# solenoid_valve_slave_circuit.net
KiCad netlist of a schematic drawn in EAGLE
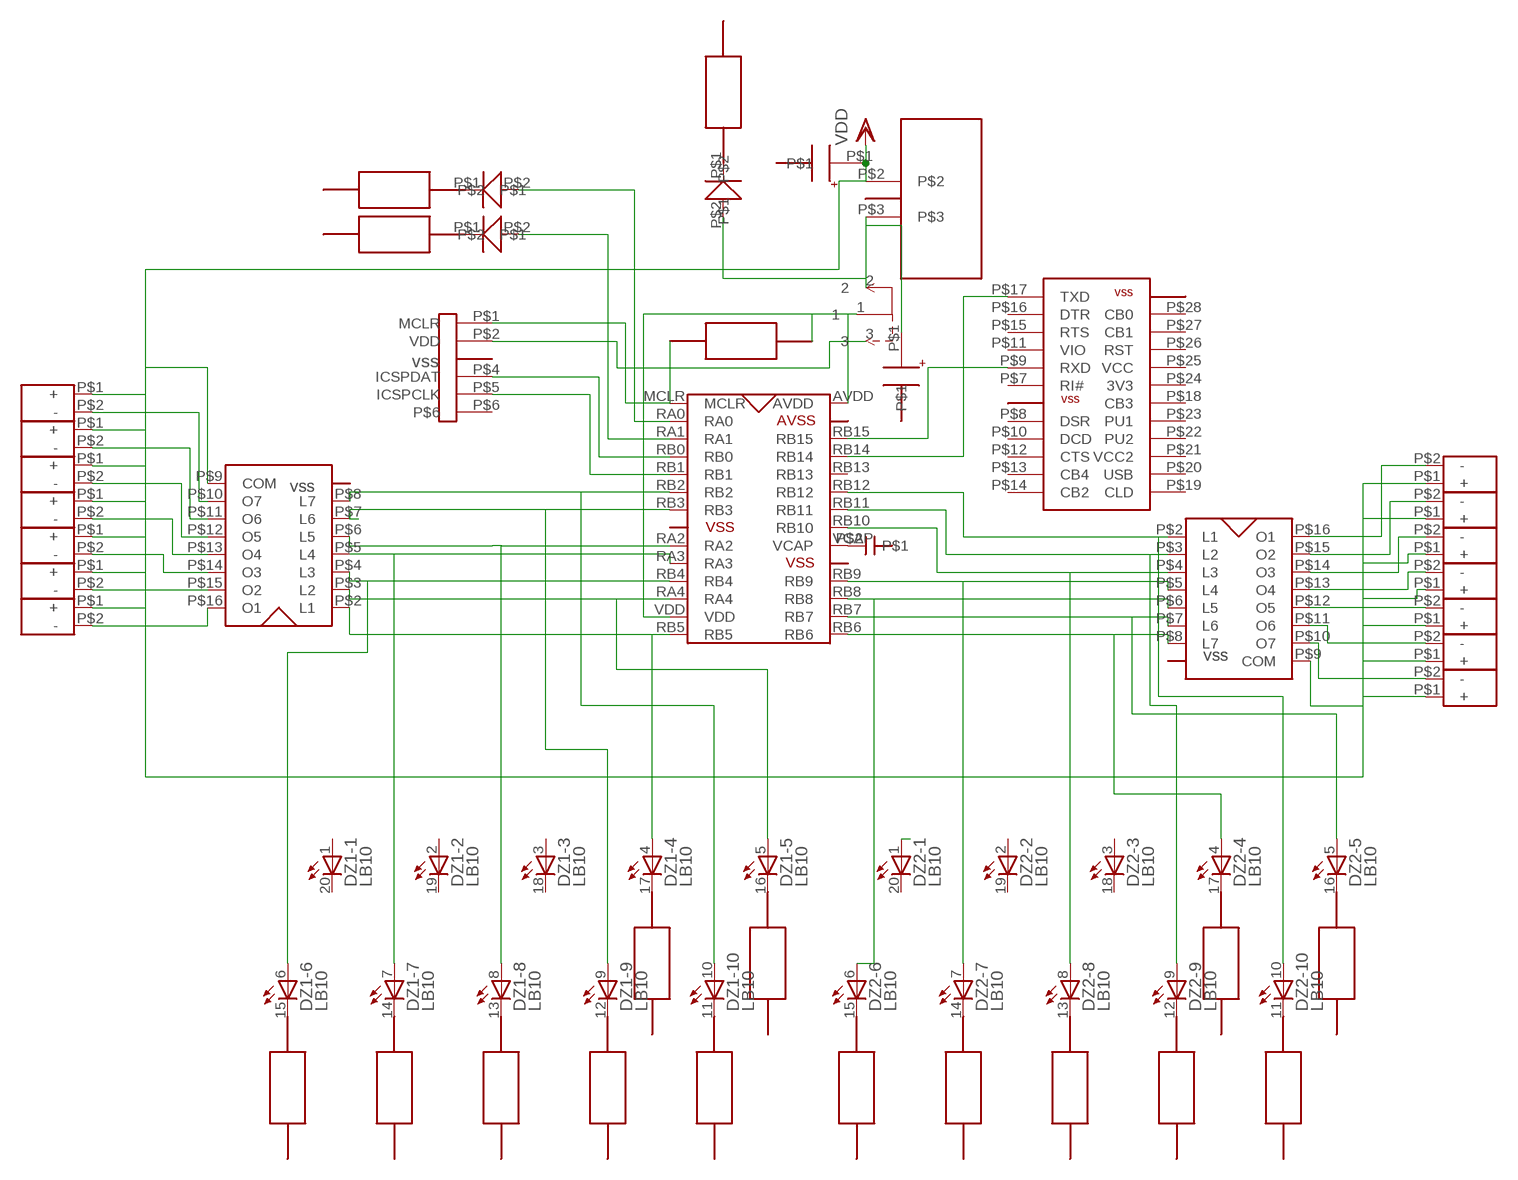
[diagram p0: schematic, sheet 1]

(export (version "E")
  (design (tool "Eeschema 10.0.6"))
  (components
    (comp (ref "DSPIC33FJ128MC1")
      (value "DSPIC33FJ128MC")
      (footprint "eagle-import:PIC_28P_2")
      (libsource (lib "eagle-import") (part "DSPIC33FJ128MC"))
    )
    (comp (ref "DZ1")
      (value "LB10")
      (footprint "eagle-import:LB10")
      (libsource (lib "eagle-import") (part "LB10"))
    )
    (comp (ref "DZ2")
      (value "LB10")
      (footprint "eagle-import:LB10")
      (libsource (lib "eagle-import") (part "LB10"))
    )
    (comp (ref "SLIDE_SWITCH1")
      (value "SLIDE_SWITCH_3")
      (footprint "eagle-import:SLIDE_SWITCH_3")
      (libsource (lib "eagle-import") (part "SLIDE_SWITCH_3"))
    )
    (comp (ref "U$1")
      (value "CAPACITOR_33")
      (footprint "eagle-import:CAPACITOR_33")
      (libsource (lib "eagle-import") (part "CAPACITOR_33"))
    )
    (comp (ref "U$2")
      (value "CHIP_RESISTOR")
      (footprint "eagle-import:CHIP_RESISTOR")
      (libsource (lib "eagle-import") (part "CHIP_RESISTOR"))
    )
    (comp (ref "U$3")
      (value "WRITER")
      (footprint "eagle-import:WRITER")
      (libsource (lib "eagle-import") (part "WRITER"))
    )
    (comp (ref "U$4")
      (value "LED")
      (footprint "eagle-import:LED")
      (libsource (lib "eagle-import") (part "LED"))
    )
    (comp (ref "U$5")
      (value "LED")
      (footprint "eagle-import:LED")
      (libsource (lib "eagle-import") (part "LED"))
    )
    (comp (ref "U$6")
      (value "CHIP_RESISTOR")
      (footprint "eagle-import:CHIP_RESISTOR")
      (libsource (lib "eagle-import") (part "CHIP_RESISTOR"))
    )
    (comp (ref "U$7")
      (value "CHIP_RESISTOR")
      (footprint "eagle-import:CHIP_RESISTOR")
      (libsource (lib "eagle-import") (part "CHIP_RESISTOR"))
    )
    (comp (ref "U$8")
      (value "TRANSISTOR_TBD62003APG")
      (footprint "eagle-import:TRANSISTOR_TBD62003APG")
      (libsource (lib "eagle-import") (part "TRANSISTOR_TBD62003APG"))
    )
    (comp (ref "U$9")
      (value "REGULATOR")
      (footprint "eagle-import:REGULATOR")
      (libsource (lib "eagle-import") (part "REGULATOR"))
    )
    (comp (ref "U$10")
      (value "TRANSISTOR_TBD62003APG")
      (footprint "eagle-import:TRANSISTOR_TBD62003APG")
      (libsource (lib "eagle-import") (part "TRANSISTOR_TBD62003APG"))
    )
    (comp (ref "U$11")
      (value "CAPACITORS_106")
      (footprint "eagle-import:CAPACITORS_106")
      (libsource (lib "eagle-import") (part "CAPACITORS_106"))
    )
    (comp (ref "U$12")
      (value "SERIALCOM")
      (footprint "eagle-import:SERIALCOM")
      (libsource (lib "eagle-import") (part "SERIALCOM"))
    )
    (comp (ref "U$13")
      (value "CHIP_RESISTOR")
      (footprint "eagle-import:CHIP_RESISTOR")
      (libsource (lib "eagle-import") (part "CHIP_RESISTOR"))
    )
    (comp (ref "U$14")
      (value "CHIP_RESISTOR")
      (footprint "eagle-import:CHIP_RESISTOR")
      (libsource (lib "eagle-import") (part "CHIP_RESISTOR"))
    )
    (comp (ref "U$15")
      (value "CHIP_RESISTOR")
      (footprint "eagle-import:CHIP_RESISTOR")
      (libsource (lib "eagle-import") (part "CHIP_RESISTOR"))
    )
    (comp (ref "U$16")
      (value "CHIP_RESISTOR")
      (footprint "eagle-import:CHIP_RESISTOR")
      (libsource (lib "eagle-import") (part "CHIP_RESISTOR"))
    )
    (comp (ref "U$17")
      (value "CHIP_RESISTOR")
      (footprint "eagle-import:CHIP_RESISTOR")
      (libsource (lib "eagle-import") (part "CHIP_RESISTOR"))
    )
    (comp (ref "U$18")
      (value "CHIP_RESISTOR")
      (footprint "eagle-import:CHIP_RESISTOR")
      (libsource (lib "eagle-import") (part "CHIP_RESISTOR"))
    )
    (comp (ref "U$19")
      (value "CHIP_RESISTOR")
      (footprint "eagle-import:CHIP_RESISTOR")
      (libsource (lib "eagle-import") (part "CHIP_RESISTOR"))
    )
    (comp (ref "U$20")
      (value "CHIP_RESISTOR")
      (footprint "eagle-import:CHIP_RESISTOR")
      (libsource (lib "eagle-import") (part "CHIP_RESISTOR"))
    )
    (comp (ref "U$21")
      (value "CHIP_RESISTOR")
      (footprint "eagle-import:CHIP_RESISTOR")
      (libsource (lib "eagle-import") (part "CHIP_RESISTOR"))
    )
    (comp (ref "U$22")
      (value "CHIP_RESISTOR")
      (footprint "eagle-import:CHIP_RESISTOR")
      (libsource (lib "eagle-import") (part "CHIP_RESISTOR"))
    )
    (comp (ref "U$23")
      (value "CHIP_RESISTOR")
      (footprint "eagle-import:CHIP_RESISTOR")
      (libsource (lib "eagle-import") (part "CHIP_RESISTOR"))
    )
    (comp (ref "U$24")
      (value "CHIP_RESISTOR")
      (footprint "eagle-import:CHIP_RESISTOR")
      (libsource (lib "eagle-import") (part "CHIP_RESISTOR"))
    )
    (comp (ref "U$25")
      (value "CHIP_RESISTOR")
      (footprint "eagle-import:CHIP_RESISTOR")
      (libsource (lib "eagle-import") (part "CHIP_RESISTOR"))
    )
    (comp (ref "U$26")
      (value "CHIP_RESISTOR")
      (footprint "eagle-import:CHIP_RESISTOR")
      (libsource (lib "eagle-import") (part "CHIP_RESISTOR"))
    )
    (comp (ref "U$27")
      (value "XHCONNECTOR_2PIN")
      (footprint "eagle-import:XHCONNECTOR_2PIN")
      (libsource (lib "eagle-import") (part "XHCONNECTOR_2PIN"))
    )
    (comp (ref "U$28")
      (value "XHCONNECTOR_2PIN")
      (footprint "eagle-import:XHCONNECTOR_2PIN")
      (libsource (lib "eagle-import") (part "XHCONNECTOR_2PIN"))
    )
    (comp (ref "U$29")
      (value "XHCONNECTOR_2PIN")
      (footprint "eagle-import:XHCONNECTOR_2PIN")
      (libsource (lib "eagle-import") (part "XHCONNECTOR_2PIN"))
    )
    (comp (ref "U$30")
      (value "XHCONNECTOR_2PIN")
      (footprint "eagle-import:XHCONNECTOR_2PIN")
      (libsource (lib "eagle-import") (part "XHCONNECTOR_2PIN"))
    )
    (comp (ref "U$31")
      (value "XHCONNECTOR_2PIN")
      (footprint "eagle-import:XHCONNECTOR_2PIN")
      (libsource (lib "eagle-import") (part "XHCONNECTOR_2PIN"))
    )
    (comp (ref "U$32")
      (value "XHCONNECTOR_2PIN")
      (footprint "eagle-import:XHCONNECTOR_2PIN")
      (libsource (lib "eagle-import") (part "XHCONNECTOR_2PIN"))
    )
    (comp (ref "U$33")
      (value "XHCONNECTOR_2PIN")
      (footprint "eagle-import:XHCONNECTOR_2PIN")
      (libsource (lib "eagle-import") (part "XHCONNECTOR_2PIN"))
    )
    (comp (ref "U$34")
      (value "XHCONNECTOR_2PIN")
      (footprint "eagle-import:XHCONNECTOR_2PIN")
      (libsource (lib "eagle-import") (part "XHCONNECTOR_2PIN"))
    )
    (comp (ref "U$35")
      (value "XHCONNECTOR_2PIN")
      (footprint "eagle-import:XHCONNECTOR_2PIN")
      (libsource (lib "eagle-import") (part "XHCONNECTOR_2PIN"))
    )
    (comp (ref "U$36")
      (value "XHCONNECTOR_2PIN")
      (footprint "eagle-import:XHCONNECTOR_2PIN")
      (libsource (lib "eagle-import") (part "XHCONNECTOR_2PIN"))
    )
    (comp (ref "U$37")
      (value "XHCONNECTOR_2PIN")
      (footprint "eagle-import:XHCONNECTOR_2PIN")
      (libsource (lib "eagle-import") (part "XHCONNECTOR_2PIN"))
    )
    (comp (ref "U$38")
      (value "XHCONNECTOR_2PIN")
      (footprint "eagle-import:XHCONNECTOR_2PIN")
      (libsource (lib "eagle-import") (part "XHCONNECTOR_2PIN"))
    )
    (comp (ref "U$39")
      (value "XHCONNECTOR_2PIN")
      (footprint "eagle-import:XHCONNECTOR_2PIN")
      (libsource (lib "eagle-import") (part "XHCONNECTOR_2PIN"))
    )
    (comp (ref "U$40")
      (value "XHCONNECTOR_2PIN")
      (footprint "eagle-import:XHCONNECTOR_2PIN")
      (libsource (lib "eagle-import") (part "XHCONNECTOR_2PIN"))
    )
    (comp (ref "U$41")
      (value "CAPACITOR_33")
      (footprint "eagle-import:CAPACITOR_33")
      (libsource (lib "eagle-import") (part "CAPACITOR_33"))
    )
    (comp (ref "U$42")
      (value "LED")
      (footprint "eagle-import:LED")
      (libsource (lib "eagle-import") (part "LED"))
    )
    (comp (ref "U$43")
      (value "CHIP_RESISTOR")
      (footprint "eagle-import:CHIP_RESISTOR")
      (libsource (lib "eagle-import") (part "CHIP_RESISTOR"))
    )
  )
  (nets
    (net (code "1") (name "Net-(DSPIC33FJ128MC1-PadAVDD)") (class "Default")
      (node (ref "DSPIC33FJ128MC1") (pin "AVDD") (pinfunction "AVDD_AVDD") (pintype "bidirectional"))
      (node (ref "DSPIC33FJ128MC1") (pin "VDD") (pinfunction "VDD_VDD") (pintype "bidirectional"))
      (node (ref "SLIDE_SWITCH1") (pin "1") (pinfunction "1_1") (pintype "bidirectional"))
    )
    (net (code "2") (name "Net-(DSPIC33FJ128MC1-PadRA0)") (class "Default")
      (node (ref "DSPIC33FJ128MC1") (pin "RA0") (pinfunction "RA0_RA0") (pintype "bidirectional"))
      (node (ref "U$4") (pin "P$2") (pinfunction "P$2_P$2") (pintype "bidirectional"))
    )
    (net (code "3") (name "Net-(DSPIC33FJ128MC1-PadRA1)") (class "Default")
      (node (ref "DSPIC33FJ128MC1") (pin "RA1") (pinfunction "RA1_RA1") (pintype "bidirectional"))
      (node (ref "U$5") (pin "P$2") (pinfunction "P$2_P$2") (pintype "bidirectional"))
    )
    (net (code "4") (name "Net-(DZ1B-A)") (class "Default")
      (node (ref "DSPIC33FJ128MC1") (pin "RB2") (pinfunction "RB2_RB2") (pintype "bidirectional"))
      (node (ref "DZ1") (pin "10") (pinfunction "A_10") (pintype "passive"))
      (node (ref "U$8") (pin "P$8") (pinfunction "L7_P$8") (pintype "bidirectional"))
    )
    (net (code "5") (name "Net-(DZ1E-A)") (class "Default")
      (node (ref "DSPIC33FJ128MC1") (pin "RB5") (pinfunction "RB5_RB5") (pintype "bidirectional"))
      (node (ref "DZ1") (pin "4") (pinfunction "A_4") (pintype "passive"))
      (node (ref "U$8") (pin "P$2") (pinfunction "L1_P$2") (pintype "bidirectional"))
    )
    (net (code "6") (name "Net-(DZ1F-A)") (class "Default")
      (node (ref "DSPIC33FJ128MC1") (pin "RA4") (pinfunction "RA4_RA4") (pintype "bidirectional"))
      (node (ref "DZ1") (pin "5") (pinfunction "A_5") (pintype "passive"))
      (node (ref "U$8") (pin "P$3") (pinfunction "L2_P$3") (pintype "bidirectional"))
    )
    (net (code "7") (name "Net-(DZ1G-A)") (class "Default")
      (node (ref "DSPIC33FJ128MC1") (pin "RB4") (pinfunction "RB4_RB4") (pintype "bidirectional"))
      (node (ref "DZ1") (pin "6") (pinfunction "A_6") (pintype "passive"))
      (node (ref "U$8") (pin "P$4") (pinfunction "L3_P$4") (pintype "bidirectional"))
    )
    (net (code "8") (name "Net-(DZ1H-A)") (class "Default")
      (node (ref "DSPIC33FJ128MC1") (pin "RA3") (pinfunction "RA3_RA3") (pintype "bidirectional"))
      (node (ref "DZ1") (pin "7") (pinfunction "A_7") (pintype "passive"))
      (node (ref "U$8") (pin "P$5") (pinfunction "L4_P$5") (pintype "bidirectional"))
    )
    (net (code "9") (name "Net-(DZ1I-A)") (class "Default")
      (node (ref "DSPIC33FJ128MC1") (pin "RA2") (pinfunction "RA2_RA2") (pintype "bidirectional"))
      (node (ref "DZ1") (pin "8") (pinfunction "A_8") (pintype "passive"))
      (node (ref "U$8") (pin "P$6") (pinfunction "L5_P$6") (pintype "bidirectional"))
    )
    (net (code "10") (name "Net-(DZ1J-A)") (class "Default")
      (node (ref "DSPIC33FJ128MC1") (pin "RB3") (pinfunction "RB3_RB3") (pintype "bidirectional"))
      (node (ref "DZ1") (pin "9") (pinfunction "A_9") (pintype "passive"))
      (node (ref "U$8") (pin "P$7") (pinfunction "L6_P$7") (pintype "bidirectional"))
    )
    (net (code "11") (name "Net-(DZ2B-A)") (class "Default")
      (node (ref "DSPIC33FJ128MC1") (pin "RB12") (pinfunction "RB12_RB12") (pintype "bidirectional"))
      (node (ref "DZ2") (pin "10") (pinfunction "A_10") (pintype "passive"))
      (node (ref "U$10") (pin "P$2") (pinfunction "L1_P$2") (pintype "bidirectional"))
    )
    (net (code "12") (name "Net-(DZ2E-A)") (class "Default")
      (node (ref "DSPIC33FJ128MC1") (pin "RB6") (pinfunction "RB6_RB6") (pintype "bidirectional"))
      (node (ref "DZ2") (pin "4") (pinfunction "A_4") (pintype "passive"))
      (node (ref "U$10") (pin "P$8") (pinfunction "L7_P$8") (pintype "bidirectional"))
    )
    (net (code "13") (name "Net-(DZ2F-A)") (class "Default")
      (node (ref "DSPIC33FJ128MC1") (pin "RB7") (pinfunction "RB7_RB7") (pintype "bidirectional"))
      (node (ref "DZ2") (pin "5") (pinfunction "A_5") (pintype "passive"))
      (node (ref "U$10") (pin "P$7") (pinfunction "L6_P$7") (pintype "bidirectional"))
    )
    (net (code "14") (name "Net-(DZ2G-A)") (class "Default")
      (node (ref "DSPIC33FJ128MC1") (pin "RB8") (pinfunction "RB8_RB8") (pintype "bidirectional"))
      (node (ref "DZ2") (pin "6") (pinfunction "A_6") (pintype "passive"))
      (node (ref "U$10") (pin "P$6") (pinfunction "L5_P$6") (pintype "bidirectional"))
    )
    (net (code "15") (name "Net-(DZ2H-A)") (class "Default")
      (node (ref "DSPIC33FJ128MC1") (pin "RB9") (pinfunction "RB9_RB9") (pintype "bidirectional"))
      (node (ref "DZ2") (pin "7") (pinfunction "A_7") (pintype "passive"))
      (node (ref "U$10") (pin "P$5") (pinfunction "L4_P$5") (pintype "bidirectional"))
    )
    (net (code "16") (name "Net-(DZ2I-A)") (class "Default")
      (node (ref "DSPIC33FJ128MC1") (pin "RB10") (pinfunction "RB10_RB10") (pintype "bidirectional"))
      (node (ref "DZ2") (pin "8") (pinfunction "A_8") (pintype "passive"))
      (node (ref "U$10") (pin "P$4") (pinfunction "L3_P$4") (pintype "bidirectional"))
    )
    (net (code "17") (name "Net-(DZ2J-A)") (class "Default")
      (node (ref "DSPIC33FJ128MC1") (pin "RB11") (pinfunction "RB11_RB11") (pintype "bidirectional"))
      (node (ref "DZ2") (pin "9") (pinfunction "A_9") (pintype "passive"))
      (node (ref "U$10") (pin "P$3") (pinfunction "L2_P$3") (pintype "bidirectional"))
    )
    (net (code "18") (name "Net-(SLIDE_SWITCH1-Pad2)") (class "Default")
      (node (ref "SLIDE_SWITCH1") (pin "2") (pinfunction "2_2") (pintype "bidirectional"))
      (node (ref "U$41") (pin "P$1") (pinfunction "P$1_P$1") (pintype "bidirectional"))
      (node (ref "U$42") (pin "P$2") (pinfunction "P$2_P$2") (pintype "bidirectional"))
      (node (ref "U$9") (pin "P$3") (pinfunction "P$3_P$3") (pintype "bidirectional"))
    )
    (net (code "19") (name "Net-(U$3-ICSPCLK)") (class "Default")
      (node (ref "DSPIC33FJ128MC1") (pin "RB1") (pinfunction "RB1_RB1") (pintype "bidirectional"))
      (node (ref "U$3") (pin "P$5") (pinfunction "ICSPCLK_P$5") (pintype "bidirectional"))
    )
    (net (code "20") (name "Net-(U$3-ICSPDAT)") (class "Default")
      (node (ref "DSPIC33FJ128MC1") (pin "RB0") (pinfunction "RB0_RB0") (pintype "bidirectional"))
      (node (ref "U$3") (pin "P$4") (pinfunction "ICSPDAT_P$4") (pintype "bidirectional"))
    )
    (net (code "21") (name "Net-(U$3-MCLR)") (class "Default")
      (node (ref "DSPIC33FJ128MC1") (pin "MCLR") (pinfunction "MCLR_MCLR") (pintype "bidirectional"))
      (node (ref "U$3") (pin "P$1") (pinfunction "MCLR_P$1") (pintype "bidirectional"))
    )
    (net (code "22") (name "Net-(U$3-VDD)") (class "Default")
      (node (ref "SLIDE_SWITCH1") (pin "3") (pinfunction "3_3") (pintype "bidirectional"))
      (node (ref "U$3") (pin "P$2") (pinfunction "VDD_P$2") (pintype "bidirectional"))
    )
    (net (code "23") (name "Net-(U$10-O1)") (class "Default")
      (node (ref "U$10") (pin "P$16") (pinfunction "O1_P$16") (pintype "bidirectional"))
      (node (ref "U$40") (pin "P$2") (pinfunction "-_P$2") (pintype "bidirectional"))
    )
    (net (code "24") (name "Net-(U$10-O2)") (class "Default")
      (node (ref "U$10") (pin "P$15") (pinfunction "O2_P$15") (pintype "bidirectional"))
      (node (ref "U$39") (pin "P$2") (pinfunction "-_P$2") (pintype "bidirectional"))
    )
    (net (code "25") (name "Net-(U$10-O3)") (class "Default")
      (node (ref "U$10") (pin "P$14") (pinfunction "O3_P$14") (pintype "bidirectional"))
      (node (ref "U$34") (pin "P$2") (pinfunction "-_P$2") (pintype "bidirectional"))
    )
    (net (code "26") (name "Net-(U$10-O4)") (class "Default")
      (node (ref "U$10") (pin "P$13") (pinfunction "O4_P$13") (pintype "bidirectional"))
      (node (ref "U$35") (pin "P$2") (pinfunction "-_P$2") (pintype "bidirectional"))
    )
    (net (code "27") (name "Net-(U$10-O5)") (class "Default")
      (node (ref "U$10") (pin "P$12") (pinfunction "O5_P$12") (pintype "bidirectional"))
      (node (ref "U$36") (pin "P$2") (pinfunction "-_P$2") (pintype "bidirectional"))
    )
    (net (code "28") (name "Net-(U$10-O6)") (class "Default")
      (node (ref "U$10") (pin "P$11") (pinfunction "O6_P$11") (pintype "bidirectional"))
      (node (ref "U$37") (pin "P$2") (pinfunction "-_P$2") (pintype "bidirectional"))
    )
    (net (code "29") (name "Net-(U$10-O7)") (class "Default")
      (node (ref "U$10") (pin "P$10") (pinfunction "O7_P$10") (pintype "bidirectional"))
      (node (ref "U$38") (pin "P$2") (pinfunction "-_P$2") (pintype "bidirectional"))
    )
    (net (code "30") (name "Net-(U$11-P$1)") (class "Default")
      (node (ref "DSPIC33FJ128MC1") (pin "VCAP") (pinfunction "VCAP_VCAP") (pintype "bidirectional"))
      (node (ref "U$11") (pin "P$2") (pinfunction "P$1_P$2") (pintype "bidirectional"))
    )
    (net (code "31") (name "Net-(U$12-RXD)") (class "Default")
      (node (ref "DSPIC33FJ128MC1") (pin "RB15") (pinfunction "RB15_RB15") (pintype "bidirectional"))
      (node (ref "U$12") (pin "P$9") (pinfunction "RXD_P$9") (pintype "bidirectional"))
    )
    (net (code "32") (name "Net-(U$12-TXD)") (class "Default")
      (node (ref "DSPIC33FJ128MC1") (pin "RB14") (pinfunction "RB14_RB14") (pintype "bidirectional"))
      (node (ref "U$12") (pin "P$17") (pinfunction "TXD_P$17") (pintype "bidirectional"))
    )
    (net (code "33") (name "Net-(U$27--)") (class "Default")
      (node (ref "U$27") (pin "P$2") (pinfunction "-_P$2") (pintype "bidirectional"))
      (node (ref "U$8") (pin "P$16") (pinfunction "O1_P$16") (pintype "bidirectional"))
    )
    (net (code "34") (name "Net-(U$28--)") (class "Default")
      (node (ref "U$28") (pin "P$2") (pinfunction "-_P$2") (pintype "bidirectional"))
      (node (ref "U$8") (pin "P$15") (pinfunction "O2_P$15") (pintype "bidirectional"))
    )
    (net (code "35") (name "Net-(U$29--)") (class "Default")
      (node (ref "U$29") (pin "P$2") (pinfunction "-_P$2") (pintype "bidirectional"))
      (node (ref "U$8") (pin "P$14") (pinfunction "O3_P$14") (pintype "bidirectional"))
    )
    (net (code "36") (name "Net-(U$30--)") (class "Default")
      (node (ref "U$30") (pin "P$2") (pinfunction "-_P$2") (pintype "bidirectional"))
      (node (ref "U$8") (pin "P$13") (pinfunction "O4_P$13") (pintype "bidirectional"))
    )
    (net (code "37") (name "Net-(U$31--)") (class "Default")
      (node (ref "U$31") (pin "P$2") (pinfunction "-_P$2") (pintype "bidirectional"))
      (node (ref "U$8") (pin "P$12") (pinfunction "O5_P$12") (pintype "bidirectional"))
    )
    (net (code "38") (name "Net-(U$32--)") (class "Default")
      (node (ref "U$32") (pin "P$2") (pinfunction "-_P$2") (pintype "bidirectional"))
      (node (ref "U$8") (pin "P$11") (pinfunction "O6_P$11") (pintype "bidirectional"))
    )
    (net (code "39") (name "Net-(U$33--)") (class "Default")
      (node (ref "U$33") (pin "P$2") (pinfunction "-_P$2") (pintype "bidirectional"))
      (node (ref "U$8") (pin "P$10") (pinfunction "O7_P$10") (pintype "bidirectional"))
    )
    (net (code "40") (name "VDD") (class "Default")
      (node (ref "U$1") (pin "P$1") (pinfunction "P$1_P$1") (pintype "bidirectional"))
      (node (ref "U$10") (pin "P$9") (pinfunction "COM_P$9") (pintype "bidirectional"))
      (node (ref "U$27") (pin "P$1") (pinfunction "+_P$1") (pintype "bidirectional"))
      (node (ref "U$28") (pin "P$1") (pinfunction "+_P$1") (pintype "bidirectional"))
      (node (ref "U$29") (pin "P$1") (pinfunction "+_P$1") (pintype "bidirectional"))
      (node (ref "U$30") (pin "P$1") (pinfunction "+_P$1") (pintype "bidirectional"))
      (node (ref "U$31") (pin "P$1") (pinfunction "+_P$1") (pintype "bidirectional"))
      (node (ref "U$32") (pin "P$1") (pinfunction "+_P$1") (pintype "bidirectional"))
      (node (ref "U$33") (pin "P$1") (pinfunction "+_P$1") (pintype "bidirectional"))
      (node (ref "U$34") (pin "P$1") (pinfunction "+_P$1") (pintype "bidirectional"))
      (node (ref "U$35") (pin "P$1") (pinfunction "+_P$1") (pintype "bidirectional"))
      (node (ref "U$36") (pin "P$1") (pinfunction "+_P$1") (pintype "bidirectional"))
      (node (ref "U$37") (pin "P$1") (pinfunction "+_P$1") (pintype "bidirectional"))
      (node (ref "U$38") (pin "P$1") (pinfunction "+_P$1") (pintype "bidirectional"))
      (node (ref "U$39") (pin "P$1") (pinfunction "+_P$1") (pintype "bidirectional"))
      (node (ref "U$40") (pin "P$1") (pinfunction "+_P$1") (pintype "bidirectional"))
      (node (ref "U$8") (pin "P$9") (pinfunction "COM_P$9") (pintype "bidirectional"))
      (node (ref "U$9") (pin "P$2") (pinfunction "P$2_P$2") (pintype "bidirectional"))
    )
    (net (code "41") (name "unconnected-(DSPIC33FJ128MC1-PadRB13)") (class "Default")
      (node (ref "DSPIC33FJ128MC1") (pin "RB13") (pinfunction "RB13_RB13") (pintype "bidirectional"))
    )
    (net (code "42") (name "unconnected-(DZ1A-A-Pad1)") (class "Default")
      (node (ref "DZ1") (pin "1") (pinfunction "A_1") (pintype "passive"))
    )
    (net (code "43") (name "unconnected-(DZ1A-C-Pad20)") (class "Default")
      (node (ref "DZ1") (pin "20") (pinfunction "C_20") (pintype "passive"))
    )
    (net (code "44") (name "unconnected-(DZ1B-C-Pad11)") (class "Default")
      (node (ref "DZ1") (pin "11") (pinfunction "C_11") (pintype "passive"))
    )
    (net (code "45") (name "unconnected-(DZ1C-A-Pad2)") (class "Default")
      (node (ref "DZ1") (pin "2") (pinfunction "A_2") (pintype "passive"))
    )
    (net (code "46") (name "unconnected-(DZ1C-C-Pad19)") (class "Default")
      (node (ref "DZ1") (pin "19") (pinfunction "C_19") (pintype "passive"))
    )
    (net (code "47") (name "unconnected-(DZ1D-A-Pad3)") (class "Default")
      (node (ref "DZ1") (pin "3") (pinfunction "A_3") (pintype "passive"))
    )
    (net (code "48") (name "unconnected-(DZ1D-C-Pad18)") (class "Default")
      (node (ref "DZ1") (pin "18") (pinfunction "C_18") (pintype "passive"))
    )
    (net (code "49") (name "unconnected-(DZ1E-C-Pad17)") (class "Default")
      (node (ref "DZ1") (pin "17") (pinfunction "C_17") (pintype "passive"))
    )
    (net (code "50") (name "unconnected-(DZ1F-C-Pad16)") (class "Default")
      (node (ref "DZ1") (pin "16") (pinfunction "C_16") (pintype "passive"))
    )
    (net (code "51") (name "unconnected-(DZ1G-C-Pad15)") (class "Default")
      (node (ref "DZ1") (pin "15") (pinfunction "C_15") (pintype "passive"))
    )
    (net (code "52") (name "unconnected-(DZ1H-C-Pad14)") (class "Default")
      (node (ref "DZ1") (pin "14") (pinfunction "C_14") (pintype "passive"))
    )
    (net (code "53") (name "unconnected-(DZ1I-C-Pad13)") (class "Default")
      (node (ref "DZ1") (pin "13") (pinfunction "C_13") (pintype "passive"))
    )
    (net (code "54") (name "unconnected-(DZ1J-C-Pad12)") (class "Default")
      (node (ref "DZ1") (pin "12") (pinfunction "C_12") (pintype "passive"))
    )
    (net (code "55") (name "unconnected-(DZ2A-A-Pad1)") (class "Default")
      (node (ref "DZ2") (pin "1") (pinfunction "A_1") (pintype "passive"))
    )
    (net (code "56") (name "unconnected-(DZ2A-C-Pad20)") (class "Default")
      (node (ref "DZ2") (pin "20") (pinfunction "C_20") (pintype "passive"))
    )
    (net (code "57") (name "unconnected-(DZ2B-C-Pad11)") (class "Default")
      (node (ref "DZ2") (pin "11") (pinfunction "C_11") (pintype "passive"))
    )
    (net (code "58") (name "unconnected-(DZ2C-A-Pad2)") (class "Default")
      (node (ref "DZ2") (pin "2") (pinfunction "A_2") (pintype "passive"))
    )
    (net (code "59") (name "unconnected-(DZ2C-C-Pad19)") (class "Default")
      (node (ref "DZ2") (pin "19") (pinfunction "C_19") (pintype "passive"))
    )
    (net (code "60") (name "unconnected-(DZ2D-A-Pad3)") (class "Default")
      (node (ref "DZ2") (pin "3") (pinfunction "A_3") (pintype "passive"))
    )
    (net (code "61") (name "unconnected-(DZ2D-C-Pad18)") (class "Default")
      (node (ref "DZ2") (pin "18") (pinfunction "C_18") (pintype "passive"))
    )
    (net (code "62") (name "unconnected-(DZ2E-C-Pad17)") (class "Default")
      (node (ref "DZ2") (pin "17") (pinfunction "C_17") (pintype "passive"))
    )
    (net (code "63") (name "unconnected-(DZ2F-C-Pad16)") (class "Default")
      (node (ref "DZ2") (pin "16") (pinfunction "C_16") (pintype "passive"))
    )
    (net (code "64") (name "unconnected-(DZ2G-C-Pad15)") (class "Default")
      (node (ref "DZ2") (pin "15") (pinfunction "C_15") (pintype "passive"))
    )
    (net (code "65") (name "unconnected-(DZ2H-C-Pad14)") (class "Default")
      (node (ref "DZ2") (pin "14") (pinfunction "C_14") (pintype "passive"))
    )
    (net (code "66") (name "unconnected-(DZ2I-C-Pad13)") (class "Default")
      (node (ref "DZ2") (pin "13") (pinfunction "C_13") (pintype "passive"))
    )
    (net (code "67") (name "unconnected-(DZ2J-C-Pad12)") (class "Default")
      (node (ref "DZ2") (pin "12") (pinfunction "C_12") (pintype "passive"))
    )
    (net (code "68") (name "unconnected-(U$3-PadP$6)") (class "Default")
      (node (ref "U$3") (pin "P$6") (pinfunction "P$6_P$6") (pintype "bidirectional"))
    )
    (net (code "69") (name "unconnected-(U$4-PadP$1)") (class "Default")
      (node (ref "U$4") (pin "P$1") (pinfunction "P$1_P$1") (pintype "bidirectional"))
    )
    (net (code "70") (name "unconnected-(U$5-PadP$1)") (class "Default")
      (node (ref "U$5") (pin "P$1") (pinfunction "P$1_P$1") (pintype "bidirectional"))
    )
    (net (code "71") (name "unconnected-(U$12-3V3-PadP$24)") (class "Default")
      (node (ref "U$12") (pin "P$24") (pinfunction "3V3_P$24") (pintype "bidirectional"))
    )
    (net (code "72") (name "unconnected-(U$12-CB0-PadP$28)") (class "Default")
      (node (ref "U$12") (pin "P$28") (pinfunction "CB0_P$28") (pintype "bidirectional"))
    )
    (net (code "73") (name "unconnected-(U$12-CB1-PadP$27)") (class "Default")
      (node (ref "U$12") (pin "P$27") (pinfunction "CB1_P$27") (pintype "bidirectional"))
    )
    (net (code "74") (name "unconnected-(U$12-CB2-PadP$14)") (class "Default")
      (node (ref "U$12") (pin "P$14") (pinfunction "CB2_P$14") (pintype "bidirectional"))
    )
    (net (code "75") (name "unconnected-(U$12-CB3-PadP$18)") (class "Default")
      (node (ref "U$12") (pin "P$18") (pinfunction "CB3_P$18") (pintype "bidirectional"))
    )
    (net (code "76") (name "unconnected-(U$12-CB4-PadP$13)") (class "Default")
      (node (ref "U$12") (pin "P$13") (pinfunction "CB4_P$13") (pintype "bidirectional"))
    )
    (net (code "77") (name "unconnected-(U$12-CLD-PadP$19)") (class "Default")
      (node (ref "U$12") (pin "P$19") (pinfunction "CLD_P$19") (pintype "bidirectional"))
    )
    (net (code "78") (name "unconnected-(U$12-CTS-PadP$12)") (class "Default")
      (node (ref "U$12") (pin "P$12") (pinfunction "CTS_P$12") (pintype "bidirectional"))
    )
    (net (code "79") (name "unconnected-(U$12-DCD-PadP$10)") (class "Default")
      (node (ref "U$12") (pin "P$10") (pinfunction "DCD_P$10") (pintype "bidirectional"))
    )
    (net (code "80") (name "unconnected-(U$12-DSR-PadP$8)") (class "Default")
      (node (ref "U$12") (pin "P$8") (pinfunction "DSR_P$8") (pintype "bidirectional"))
    )
    (net (code "81") (name "unconnected-(U$12-DTR-PadP$16)") (class "Default")
      (node (ref "U$12") (pin "P$16") (pinfunction "DTR_P$16") (pintype "bidirectional"))
    )
    (net (code "82") (name "unconnected-(U$12-PU1-PadP$23)") (class "Default")
      (node (ref "U$12") (pin "P$23") (pinfunction "PU1_P$23") (pintype "bidirectional"))
    )
    (net (code "83") (name "unconnected-(U$12-PU2-PadP$22)") (class "Default")
      (node (ref "U$12") (pin "P$22") (pinfunction "PU2_P$22") (pintype "bidirectional"))
    )
    (net (code "84") (name "unconnected-(U$12-RI#-PadP$7)") (class "Default")
      (node (ref "U$12") (pin "P$7") (pinfunction "RI#_P$7") (pintype "bidirectional"))
    )
    (net (code "85") (name "unconnected-(U$12-RST-PadP$26)") (class "Default")
      (node (ref "U$12") (pin "P$26") (pinfunction "RST_P$26") (pintype "bidirectional"))
    )
    (net (code "86") (name "unconnected-(U$12-RTS-PadP$15)") (class "Default")
      (node (ref "U$12") (pin "P$15") (pinfunction "RTS_P$15") (pintype "bidirectional"))
    )
    (net (code "87") (name "unconnected-(U$12-USB-PadP$20)") (class "Default")
      (node (ref "U$12") (pin "P$20") (pinfunction "USB_P$20") (pintype "bidirectional"))
    )
    (net (code "88") (name "unconnected-(U$12-VCC-PadP$25)") (class "Default")
      (node (ref "U$12") (pin "P$25") (pinfunction "VCC_P$25") (pintype "bidirectional"))
    )
    (net (code "89") (name "unconnected-(U$12-VCC2-PadP$21)") (class "Default")
      (node (ref "U$12") (pin "P$21") (pinfunction "VCC2_P$21") (pintype "bidirectional"))
    )
    (net (code "90") (name "unconnected-(U$12-VIO-PadP$11)") (class "Default")
      (node (ref "U$12") (pin "P$11") (pinfunction "VIO_P$11") (pintype "bidirectional"))
    )
    (net (code "91") (name "unconnected-(U$42-PadP$1)") (class "Default")
      (node (ref "U$42") (pin "P$1") (pinfunction "P$1_P$1") (pintype "bidirectional"))
    )
  )
)
